# Mother_Board_Power.net
KiCad netlist of a schematic drawn in Altium Designer
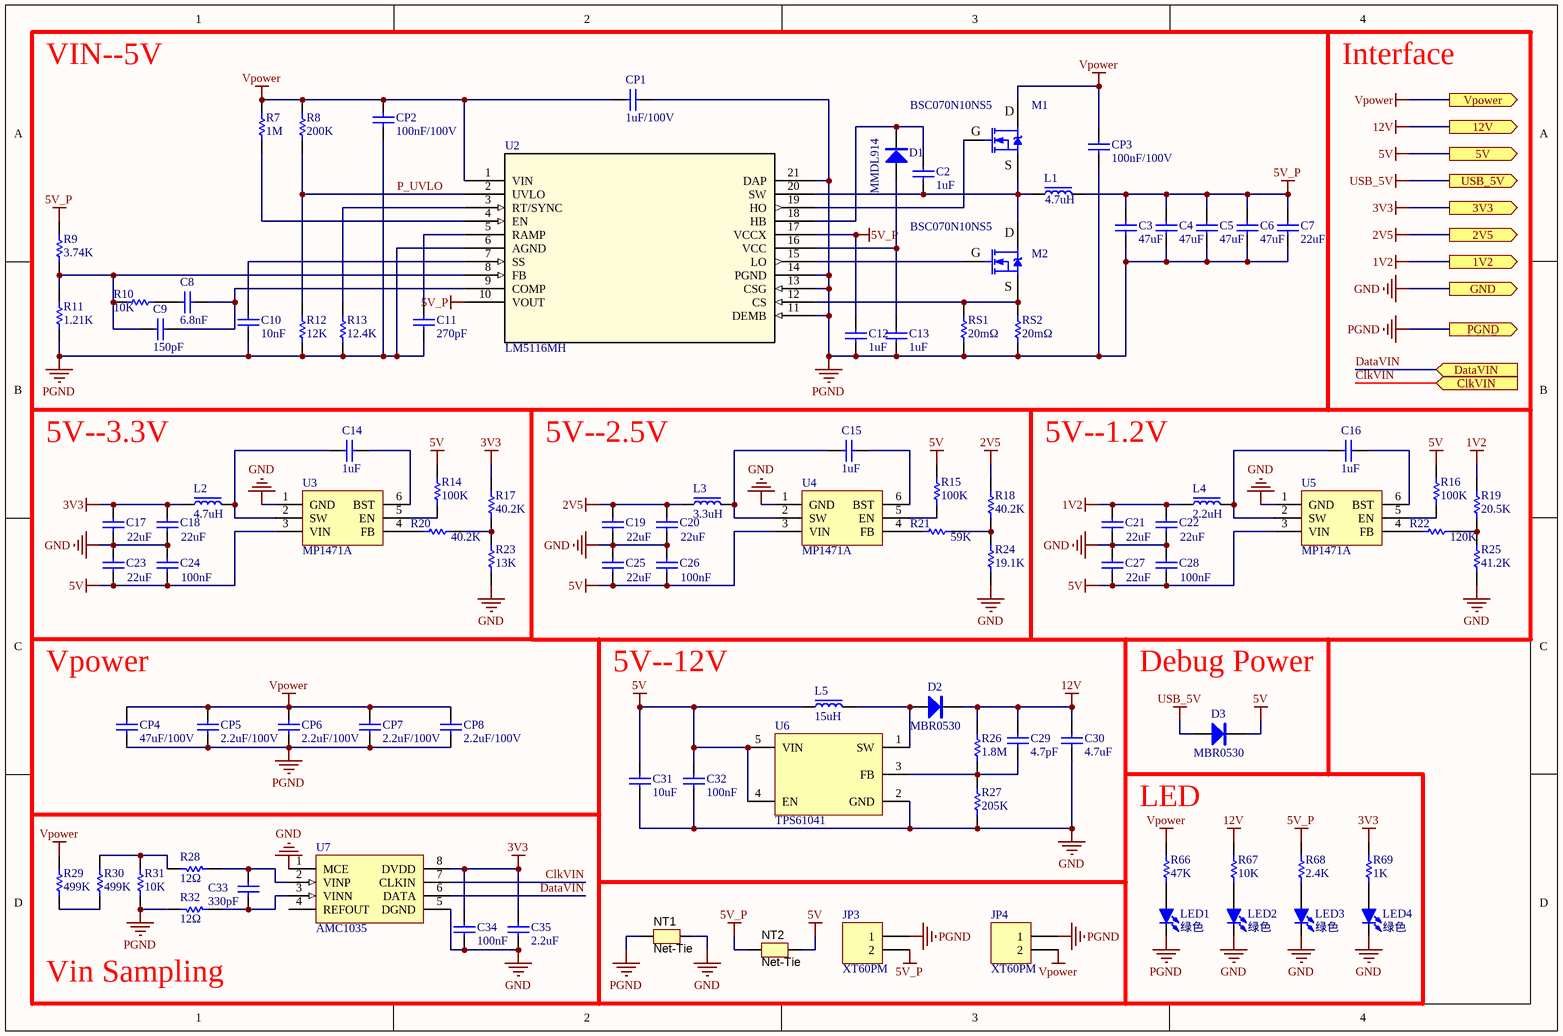
[diagram p0: Mother Board Power.SchDoc]

(export (version "E")
  (design (tool "Eeschema 10.0.6"))
  (components
    (comp (ref "C2") (value "1uF") (footprint "C0805") (libsource (lib "Cap") (part "Cap")))
    (comp (ref "C3") (value "47uF") (footprint "C0805") (libsource (lib "Cap") (part "Cap")))
    (comp (ref "C4") (value "47uF") (footprint "C0805") (libsource (lib "Cap") (part "Cap")))
    (comp (ref "C5") (value "47uF") (footprint "C0805") (libsource (lib "Cap") (part "Cap")))
    (comp (ref "C6") (value "47uF") (footprint "C0805") (libsource (lib "Cap") (part "Cap")))
    (comp (ref "C7") (value "22uF") (footprint "C0805") (libsource (lib "Cap") (part "Cap")))
    (comp (ref "C8") (value "6.8nF") (footprint "C0603") (libsource (lib "Cap") (part "Cap")))
    (comp (ref "C9") (value "150pF") (footprint "C0603") (libsource (lib "Cap") (part "Cap")))
    (comp (ref "C10") (value "10nF") (footprint "C0603") (libsource (lib "Cap") (part "Cap")))
    (comp (ref "C11") (value "270pF") (footprint "C0603") (libsource (lib "Cap") (part "Cap")))
    (comp (ref "C12") (value "1uF") (footprint "C0805") (libsource (lib "Cap") (part "Cap")))
    (comp (ref "C13") (value "1uF") (footprint "C0805") (libsource (lib "Cap") (part "Cap")))
    (comp (ref "C14") (value "1uF") (footprint "C0603") (libsource (lib "Cap") (part "Cap")))
    (comp (ref "C15") (value "1uF") (footprint "C0603") (libsource (lib "Cap") (part "Cap")))
    (comp (ref "C16") (value "1uF") (footprint "C0603") (libsource (lib "Cap") (part "Cap")))
    (comp (ref "C17") (value "22uF") (footprint "C0805") (libsource (lib "Cap") (part "Cap")))
    (comp (ref "C18") (value "22uF") (footprint "C0805") (libsource (lib "Cap") (part "Cap")))
    (comp (ref "C19") (value "22uF") (footprint "C0805") (libsource (lib "Cap") (part "Cap")))
    (comp (ref "C20") (value "22uF") (footprint "C0805") (libsource (lib "Cap") (part "Cap")))
    (comp (ref "C21") (value "22uF") (footprint "C0805") (libsource (lib "Cap") (part "Cap")))
    (comp (ref "C22") (value "22uF") (footprint "C0805") (libsource (lib "Cap") (part "Cap")))
    (comp (ref "C23") (value "22uF") (footprint "C0805") (libsource (lib "Cap") (part "Cap")))
    (comp (ref "C24") (value "100nF") (footprint "C0603") (libsource (lib "Cap") (part "Cap")))
    (comp (ref "C25") (value "22uF") (footprint "C0805") (libsource (lib "Cap") (part "Cap")))
    (comp (ref "C26") (value "100nF") (footprint "C0603") (libsource (lib "Cap") (part "Cap")))
    (comp (ref "C27") (value "22uF") (footprint "C0805") (libsource (lib "Cap") (part "Cap")))
    (comp (ref "C28") (value "100nF") (footprint "C0603") (libsource (lib "Cap") (part "Cap")))
    (comp (ref "C29") (value "4.7pF") (footprint "C0603") (libsource (lib "Cap") (part "Cap")))
    (comp (ref "C30") (value "4.7uF") (footprint "C0805") (libsource (lib "Cap") (part "Cap")))
    (comp (ref "C31") (value "10uF") (footprint "C0805") (libsource (lib "Cap") (part "Cap")))
    (comp (ref "C32") (value "100nF") (footprint "C0603") (libsource (lib "Cap") (part "Cap")))
    (comp (ref "C33") (value "330pF") (footprint "C0603") (libsource (lib "Cap") (part "Cap")))
    (comp (ref "C34") (value "100nF") (footprint "C0603") (libsource (lib "Cap") (part "Cap")))
    (comp (ref "C35") (value "2.2uF") (footprint "C0603") (libsource (lib "Cap") (part "Cap")))
    (comp (ref "CP1") (value "1uF/100V") (footprint "C1206") (libsource (lib "Cap") (part "Cap")))
    (comp (ref "CP2") (value "100nF/100V") (footprint "C1206") (libsource (lib "Cap") (part "Cap")))
    (comp (ref "CP3") (value "100nF/100V") (footprint "C1206") (libsource (lib "Cap") (part "Cap")))
    (comp (ref "CP4") (value "47uF/100V") (footprint "C1206") (libsource (lib "Cap") (part "Cap")))
    (comp (ref "CP5") (value "2.2uF/100V") (footprint "C1206") (libsource (lib "Cap") (part "Cap")))
    (comp (ref "CP6") (value "2.2uF/100V") (footprint "C1206") (libsource (lib "Cap") (part "Cap")))
    (comp (ref "CP7") (value "2.2uF/100V") (footprint "C1206") (libsource (lib "Cap") (part "Cap")))
    (comp (ref "CP8") (value "2.2uF/100V") (footprint "C1206") (libsource (lib "Cap") (part "Cap")))
    (comp (ref "D1")
      (value "MMDL914")
      (footprint "SOD-323")
      (description "100V 0.2A开关管")
      (libsource (lib "All lib") (part "MMDL914"))
    )
    (comp (ref "D2")
      (value "MBR0530")
      (footprint "SOD-123")
      (description "30V 0.5A")
      (libsource (lib "All lib") (part "MBR0530"))
    )
    (comp (ref "D3")
      (value "MBR0530")
      (footprint "SOD-123")
      (description "30V 0.5A")
      (libsource (lib "All lib") (part "MBR0530"))
    )
    (comp (ref "JP3") (value "XT60PM") (footprint "XT60PM") (libsource (lib "All lib") (part "XT60PM")))
    (comp (ref "JP4") (value "XT60PM") (footprint "XT60PM") (libsource (lib "All lib") (part "XT60PM")))
    (comp (ref "L1")
      (value "4.7uH")
      (footprint "L 1040")
      (description "功率屏蔽电感")
      (libsource (lib "All lib") (part "L-CDRH"))
    )
    (comp (ref "L2")
      (value "4.7uH")
      (footprint "L 0530")
      (description "功率屏蔽电感")
      (libsource (lib "All lib") (part "L-CDRH"))
    )
    (comp (ref "L3")
      (value "3.3uH")
      (footprint "L 0530")
      (description "功率屏蔽电感")
      (libsource (lib "All lib") (part "L-CDRH"))
    )
    (comp (ref "L4")
      (value "2.2uH")
      (footprint "L 0530")
      (description "功率屏蔽电感")
      (libsource (lib "All lib") (part "L-CDRH"))
    )
    (comp (ref "L5")
      (value "15uH")
      (footprint "L 0530")
      (description "功率屏蔽电感")
      (libsource (lib "All lib") (part "L-CDRH"))
    )
    (comp (ref "LED1")
      (value "绿色")
      (footprint "LED 0603G L")
      (description "贴片LED")
      (fields (field (name "版权归属") "源创客"))
      (libsource (lib "All lib") (part "LED-SMD"))
    )
    (comp (ref "LED2")
      (value "绿色")
      (footprint "LED 0603G L")
      (description "贴片LED")
      (fields (field (name "版权归属") "源创客"))
      (libsource (lib "All lib") (part "LED-SMD"))
    )
    (comp (ref "LED3")
      (value "绿色")
      (footprint "LED 0603G L")
      (description "贴片LED")
      (fields (field (name "版权归属") "源创客"))
      (libsource (lib "All lib") (part "LED-SMD"))
    )
    (comp (ref "LED4")
      (value "绿色")
      (footprint "LED 0603G L")
      (description "贴片LED")
      (fields (field (name "版权归属") "源创客"))
      (libsource (lib "All lib") (part "LED-SMD"))
    )
    (comp (ref "M1")
      (value "BSC070N10NS5")
      (footprint "TDSON-8")
      (description "N沟场效应管")
      (libsource (lib "All lib") (part "BSC070N10NS5"))
    )
    (comp (ref "M2")
      (value "BSC070N10NS5")
      (footprint "TDSON-8")
      (description "N沟场效应管")
      (libsource (lib "All lib") (part "BSC070N10NS5"))
    )
    (comp (ref "NT1")
      (value "Net-Tie")
      (footprint "Net-Tie_80mil")
      (description "Single point connection between nets.")
      (fields (field (name "SYMBOLCREATOR") "codlsc") (field (name "PUBLISHER") "Texas Instruments"))
      (libsource (lib "All lib") (part "Net-Tie"))
    )
    (comp (ref "NT2")
      (value "Net-Tie")
      (footprint "Net-Tie_80mil")
      (description "Single point connection between nets.")
      (fields (field (name "SYMBOLCREATOR") "codlsc") (field (name "PUBLISHER") "Texas Instruments"))
      (libsource (lib "All lib") (part "Net-Tie"))
    )
    (comp (ref "R7") (value "1M") (footprint "R0603") (libsource (lib "Res") (part "RES")))
    (comp (ref "R8") (value "200K") (footprint "R0603") (libsource (lib "Res") (part "RES")))
    (comp (ref "R9") (value "3.74K") (footprint "R0603") (libsource (lib "Res") (part "RES")))
    (comp (ref "R10") (value "10K") (footprint "R0603") (libsource (lib "Res") (part "RES")))
    (comp (ref "R11") (value "1.21K") (footprint "R0603") (libsource (lib "Res") (part "RES")))
    (comp (ref "R12") (value "12K") (footprint "R0603") (libsource (lib "Res") (part "RES")))
    (comp (ref "R13") (value "12.4K") (footprint "R0603") (libsource (lib "Res") (part "RES")))
    (comp (ref "R14") (value "100K") (footprint "R0603") (libsource (lib "Res") (part "RES")))
    (comp (ref "R15") (value "100K") (footprint "R0603") (libsource (lib "Res") (part "RES")))
    (comp (ref "R16") (value "100K") (footprint "R0603") (libsource (lib "Res") (part "RES")))
    (comp (ref "R17") (value "40.2K") (footprint "R0603") (libsource (lib "Res") (part "RES")))
    (comp (ref "R18") (value "40.2K") (footprint "R0603") (libsource (lib "Res") (part "RES")))
    (comp (ref "R19") (value "20.5K") (footprint "R0603") (libsource (lib "Res") (part "RES")))
    (comp (ref "R20") (value "40.2K") (footprint "R0603") (libsource (lib "Res") (part "RES")))
    (comp (ref "R21") (value "59K") (footprint "R0603") (libsource (lib "Res") (part "RES")))
    (comp (ref "R22") (value "120K") (footprint "R0603") (libsource (lib "Res") (part "RES")))
    (comp (ref "R23") (value "13K") (footprint "R0603") (libsource (lib "Res") (part "RES")))
    (comp (ref "R24") (value "19.1K") (footprint "R0603") (libsource (lib "Res") (part "RES")))
    (comp (ref "R25") (value "41.2K") (footprint "R0603") (libsource (lib "Res") (part "RES")))
    (comp (ref "R26") (value "1.8M") (footprint "R0603") (libsource (lib "Res") (part "RES")))
    (comp (ref "R27") (value "205K") (footprint "R0603") (libsource (lib "Res") (part "RES")))
    (comp (ref "R28") (value "12Ω") (footprint "R0603") (libsource (lib "Res") (part "RES")))
    (comp (ref "R29") (value "499K") (footprint "R0603") (libsource (lib "Res") (part "RES")))
    (comp (ref "R30") (value "499K") (footprint "R0603") (libsource (lib "Res") (part "RES")))
    (comp (ref "R31") (value "10K") (footprint "R0603") (libsource (lib "Res") (part "RES")))
    (comp (ref "R32") (value "12Ω") (footprint "R0603") (libsource (lib "Res") (part "RES")))
    (comp (ref "R66") (value "47K") (footprint "R0603") (libsource (lib "Res") (part "RES")))
    (comp (ref "R67") (value "10K") (footprint "R0603") (libsource (lib "Res") (part "RES")))
    (comp (ref "R68") (value "2.4K") (footprint "R0603") (libsource (lib "Res") (part "RES")))
    (comp (ref "R69") (value "1K") (footprint "R0603") (libsource (lib "Res") (part "RES")))
    (comp (ref "RS1") (value "20mΩ") (footprint "R1206") (libsource (lib "Res") (part "RES")))
    (comp (ref "RS2") (value "20mΩ") (footprint "R1206") (libsource (lib "Res") (part "RES")))
    (comp (ref "U2")
      (value "LM5116MH")
      (footprint "MXA20A_TEX-L")
      (description "No Description Available")
      (fields (field (name "COPYRIGHT") "Copyright (C) 2021 Ultra Librarian. All rights reserved."))
      (libsource (lib "All lib") (part "LM5116MH"))
    )
    (comp (ref "U3")
      (value "MP1471A")
      (footprint "SOT23-6L")
      (description "4.5-16V输入 DC-DC Buck 芯片")
      (libsource (lib "All lib") (part "MP1471A"))
    )
    (comp (ref "U4")
      (value "MP1471A")
      (footprint "SOT23-6L")
      (description "4.5-16V输入 DC-DC Buck 芯片")
      (libsource (lib "All lib") (part "MP1471A"))
    )
    (comp (ref "U5")
      (value "MP1471A")
      (footprint "SOT23-6L")
      (description "4.5-16V输入 DC-DC Buck 芯片")
      (libsource (lib "All lib") (part "MP1471A"))
    )
    (comp (ref "U6")
      (value "TPS61041")
      (footprint "SOT23-5L")
      (description "Boost DC-DC")
      (libsource (lib "All lib") (part "TPS6104x"))
    )
    (comp (ref "U7") (value "AMC1035") (footprint "SOP8_L") (libsource (lib "All lib") (part "AMC1035")))
  )
  (nets
    (net (code "1") (name "/ClkVIN") (class "Default")
      (node (ref "U7") (pin "7") (pinfunction "CLKIN_7") (pintype "passive"))
    )
    (net (code "2") (name "/DataVIN") (class "Default")
      (node (ref "U7") (pin "6") (pinfunction "DATA_6") (pintype "power_in"))
    )
    (net (code "3") (name "/P_UVLO") (class "Default")
      (node (ref "R12") (pin "1") (pinfunction "1_1") (pintype "passive"))
      (node (ref "R8") (pin "1") (pinfunction "1_1") (pintype "passive"))
      (node (ref "U2") (pin "2") (pinfunction "UVLO_2") (pintype "passive"))
    )
    (net (code "4") (name "1V2") (class "Default")
      (node (ref "C21") (pin "1") (pinfunction "1_1") (pintype "passive"))
      (node (ref "C22") (pin "1") (pinfunction "1_1") (pintype "passive"))
      (node (ref "L4") (pin "1") (pinfunction "1_1") (pintype "passive"))
      (node (ref "R19") (pin "2") (pinfunction "2_2") (pintype "passive"))
    )
    (net (code "5") (name "2V5") (class "Default")
      (node (ref "C19") (pin "1") (pinfunction "1_1") (pintype "passive"))
      (node (ref "C20") (pin "1") (pinfunction "1_1") (pintype "passive"))
      (node (ref "L3") (pin "1") (pinfunction "1_1") (pintype "passive"))
      (node (ref "R18") (pin "2") (pinfunction "2_2") (pintype "passive"))
    )
    (net (code "6") (name "3V3") (class "Default")
      (node (ref "C17") (pin "1") (pinfunction "1_1") (pintype "passive"))
      (node (ref "C18") (pin "1") (pinfunction "1_1") (pintype "passive"))
      (node (ref "C34") (pin "1") (pinfunction "1_1") (pintype "passive"))
      (node (ref "C35") (pin "1") (pinfunction "1_1") (pintype "passive"))
      (node (ref "L2") (pin "1") (pinfunction "1_1") (pintype "passive"))
      (node (ref "R17") (pin "2") (pinfunction "2_2") (pintype "passive"))
      (node (ref "R69") (pin "1") (pinfunction "1_1") (pintype "passive"))
      (node (ref "U7") (pin "8") (pinfunction "DVDD_8") (pintype "power_in"))
    )
    (net (code "7") (name "5V") (class "Default")
      (node (ref "C23") (pin "2") (pinfunction "2_2") (pintype "passive"))
      (node (ref "C24") (pin "2") (pinfunction "2_2") (pintype "passive"))
      (node (ref "C25") (pin "2") (pinfunction "2_2") (pintype "passive"))
      (node (ref "C26") (pin "2") (pinfunction "2_2") (pintype "passive"))
      (node (ref "C27") (pin "2") (pinfunction "2_2") (pintype "passive"))
      (node (ref "C28") (pin "2") (pinfunction "2_2") (pintype "passive"))
      (node (ref "C31") (pin "2") (pinfunction "2_2") (pintype "passive"))
      (node (ref "C32") (pin "2") (pinfunction "2_2") (pintype "passive"))
      (node (ref "D3") (pin "K") (pinfunction "K_K") (pintype "passive"))
      (node (ref "L5") (pin "1") (pinfunction "1_1") (pintype "passive"))
      (node (ref "NT2") (pin "2") (pinfunction "2_2") (pintype "passive"))
      (node (ref "R14") (pin "1") (pinfunction "1_1") (pintype "passive"))
      (node (ref "R15") (pin "1") (pinfunction "1_1") (pintype "passive"))
      (node (ref "R16") (pin "1") (pinfunction "1_1") (pintype "passive"))
      (node (ref "U3") (pin "3") (pinfunction "VIN_3") (pintype "power_in"))
      (node (ref "U4") (pin "3") (pinfunction "VIN_3") (pintype "power_in"))
      (node (ref "U5") (pin "3") (pinfunction "VIN_3") (pintype "power_in"))
      (node (ref "U6") (pin "4") (pinfunction "EN_4") (pintype "passive"))
      (node (ref "U6") (pin "5") (pinfunction "VIN_5") (pintype "passive"))
    )
    (net (code "8") (name "5V_P") (class "Default")
      (node (ref "C12") (pin "1") (pinfunction "1_1") (pintype "passive"))
      (node (ref "C3") (pin "1") (pinfunction "1_1") (pintype "passive"))
      (node (ref "C4") (pin "1") (pinfunction "1_1") (pintype "passive"))
      (node (ref "C5") (pin "1") (pinfunction "1_1") (pintype "passive"))
      (node (ref "C6") (pin "1") (pinfunction "1_1") (pintype "passive"))
      (node (ref "C7") (pin "1") (pinfunction "1_1") (pintype "passive"))
      (node (ref "JP3") (pin "2") (pinfunction "2_2") (pintype "passive"))
      (node (ref "L1") (pin "2") (pinfunction "2_2") (pintype "passive"))
      (node (ref "NT2") (pin "1") (pinfunction "1_1") (pintype "passive"))
      (node (ref "R68") (pin "1") (pinfunction "1_1") (pintype "passive"))
      (node (ref "R9") (pin "2") (pinfunction "2_2") (pintype "passive"))
      (node (ref "U2") (pin "10") (pinfunction "VOUT_10") (pintype "passive"))
      (node (ref "U2") (pin "17") (pinfunction "VCCX_17") (pintype "power_in"))
    )
    (net (code "9") (name "12V") (class "Default")
      (node (ref "C29") (pin "2") (pinfunction "2_2") (pintype "passive"))
      (node (ref "C30") (pin "2") (pinfunction "2_2") (pintype "passive"))
      (node (ref "D2") (pin "K") (pinfunction "K_K") (pintype "passive"))
      (node (ref "R26") (pin "1") (pinfunction "1_1") (pintype "passive"))
      (node (ref "R67") (pin "1") (pinfunction "1_1") (pintype "passive"))
    )
    (net (code "10") (name "GND") (class "Default")
      (node (ref "C17") (pin "2") (pinfunction "2_2") (pintype "passive"))
      (node (ref "C18") (pin "2") (pinfunction "2_2") (pintype "passive"))
      (node (ref "C19") (pin "2") (pinfunction "2_2") (pintype "passive"))
      (node (ref "C20") (pin "2") (pinfunction "2_2") (pintype "passive"))
      (node (ref "C21") (pin "2") (pinfunction "2_2") (pintype "passive"))
      (node (ref "C22") (pin "2") (pinfunction "2_2") (pintype "passive"))
      (node (ref "C23") (pin "1") (pinfunction "1_1") (pintype "passive"))
      (node (ref "C24") (pin "1") (pinfunction "1_1") (pintype "passive"))
      (node (ref "C25") (pin "1") (pinfunction "1_1") (pintype "passive"))
      (node (ref "C26") (pin "1") (pinfunction "1_1") (pintype "passive"))
      (node (ref "C27") (pin "1") (pinfunction "1_1") (pintype "passive"))
      (node (ref "C28") (pin "1") (pinfunction "1_1") (pintype "passive"))
      (node (ref "C30") (pin "1") (pinfunction "1_1") (pintype "passive"))
      (node (ref "C31") (pin "1") (pinfunction "1_1") (pintype "passive"))
      (node (ref "C32") (pin "1") (pinfunction "1_1") (pintype "passive"))
      (node (ref "C34") (pin "2") (pinfunction "2_2") (pintype "passive"))
      (node (ref "C35") (pin "2") (pinfunction "2_2") (pintype "passive"))
      (node (ref "LED2") (pin "K") (pinfunction "K_K") (pintype "passive"))
      (node (ref "LED3") (pin "K") (pinfunction "K_K") (pintype "passive"))
      (node (ref "LED4") (pin "K") (pinfunction "K_K") (pintype "passive"))
      (node (ref "NT1") (pin "2") (pinfunction "2_2") (pintype "passive"))
      (node (ref "R23") (pin "2") (pinfunction "2_2") (pintype "passive"))
      (node (ref "R24") (pin "2") (pinfunction "2_2") (pintype "passive"))
      (node (ref "R25") (pin "2") (pinfunction "2_2") (pintype "passive"))
      (node (ref "R27") (pin "2") (pinfunction "2_2") (pintype "passive"))
      (node (ref "U3") (pin "1") (pinfunction "GND_1") (pintype "power_in"))
      (node (ref "U4") (pin "1") (pinfunction "GND_1") (pintype "power_in"))
      (node (ref "U5") (pin "1") (pinfunction "GND_1") (pintype "power_in"))
      (node (ref "U6") (pin "2") (pinfunction "GND_2") (pintype "passive"))
      (node (ref "U7") (pin "1") (pinfunction "MCE_1") (pintype "power_in"))
      (node (ref "U7") (pin "5") (pinfunction "DGND_5") (pintype "power_in"))
    )
    (net (code "11") (name "Net-(C8-Pad1)") (class "Default")
      (node (ref "C8") (pin "1") (pinfunction "1_1") (pintype "passive"))
      (node (ref "R10") (pin "2") (pinfunction "2_2") (pintype "passive"))
    )
    (net (code "12") (name "Net-(LED1-PadA)") (class "Default")
      (node (ref "LED1") (pin "A") (pinfunction "A_A") (pintype "passive"))
      (node (ref "R66") (pin "2") (pinfunction "2_2") (pintype "passive"))
    )
    (net (code "13") (name "Net-(LED2-PadA)") (class "Default")
      (node (ref "LED2") (pin "A") (pinfunction "A_A") (pintype "passive"))
      (node (ref "R67") (pin "2") (pinfunction "2_2") (pintype "passive"))
    )
    (net (code "14") (name "Net-(LED3-PadA)") (class "Default")
      (node (ref "LED3") (pin "A") (pinfunction "A_A") (pintype "passive"))
      (node (ref "R68") (pin "2") (pinfunction "2_2") (pintype "passive"))
    )
    (net (code "15") (name "Net-(LED4-PadA)") (class "Default")
      (node (ref "LED4") (pin "A") (pinfunction "A_A") (pintype "passive"))
      (node (ref "R69") (pin "2") (pinfunction "2_2") (pintype "passive"))
    )
    (net (code "16") (name "Net-(R17-Pad1)") (class "Default")
      (node (ref "R17") (pin "1") (pinfunction "1_1") (pintype "passive"))
      (node (ref "R20") (pin "1") (pinfunction "1_1") (pintype "passive"))
      (node (ref "R23") (pin "1") (pinfunction "1_1") (pintype "passive"))
    )
    (net (code "17") (name "Net-(R18-Pad1)") (class "Default")
      (node (ref "R18") (pin "1") (pinfunction "1_1") (pintype "passive"))
      (node (ref "R21") (pin "1") (pinfunction "1_1") (pintype "passive"))
      (node (ref "R24") (pin "1") (pinfunction "1_1") (pintype "passive"))
    )
    (net (code "18") (name "Net-(R19-Pad1)") (class "Default")
      (node (ref "R19") (pin "1") (pinfunction "1_1") (pintype "passive"))
      (node (ref "R22") (pin "1") (pinfunction "1_1") (pintype "passive"))
      (node (ref "R25") (pin "1") (pinfunction "1_1") (pintype "passive"))
    )
    (net (code "19") (name "Net-(R28-Pad1)") (class "Default")
      (node (ref "R28") (pin "1") (pinfunction "1_1") (pintype "passive"))
      (node (ref "R30") (pin "1") (pinfunction "1_1") (pintype "passive"))
      (node (ref "R31") (pin "2") (pinfunction "2_2") (pintype "passive"))
    )
    (net (code "20") (name "Net-(R29-Pad1)") (class "Default")
      (node (ref "R29") (pin "1") (pinfunction "1_1") (pintype "passive"))
      (node (ref "R30") (pin "2") (pinfunction "2_2") (pintype "passive"))
    )
    (net (code "21") (name "Net-(U2-COMP)") (class "Default")
      (node (ref "C8") (pin "2") (pinfunction "2_2") (pintype "passive"))
      (node (ref "C9") (pin "2") (pinfunction "2_2") (pintype "passive"))
      (node (ref "U2") (pin "9") (pinfunction "COMP_9") (pintype "passive"))
    )
    (net (code "22") (name "Net-(U2-CS)") (class "Default")
      (node (ref "M2") (pin "S") (pinfunction "S_S") (pintype "passive"))
      (node (ref "RS1") (pin "2") (pinfunction "2_2") (pintype "passive"))
      (node (ref "RS2") (pin "2") (pinfunction "2_2") (pintype "passive"))
      (node (ref "U2") (pin "12") (pinfunction "CS_12") (pintype "input"))
    )
    (net (code "23") (name "Net-(U2-EN)") (class "Default")
      (node (ref "R7") (pin "2") (pinfunction "2_2") (pintype "passive"))
      (node (ref "U2") (pin "4") (pinfunction "EN_4") (pintype "input"))
    )
    (net (code "24") (name "Net-(U2-FB)") (class "Default")
      (node (ref "C9") (pin "1") (pinfunction "1_1") (pintype "passive"))
      (node (ref "R10") (pin "1") (pinfunction "1_1") (pintype "passive"))
      (node (ref "R11") (pin "1") (pinfunction "1_1") (pintype "passive"))
      (node (ref "R9") (pin "1") (pinfunction "1_1") (pintype "passive"))
      (node (ref "U2") (pin "8") (pinfunction "FB_8") (pintype "input"))
    )
    (net (code "25") (name "Net-(U2-HB)") (class "Default")
      (node (ref "C2") (pin "2") (pinfunction "2_2") (pintype "passive"))
      (node (ref "D1") (pin "K") (pinfunction "K_K") (pintype "passive"))
      (node (ref "U2") (pin "18") (pinfunction "HB_18") (pintype "passive"))
    )
    (net (code "26") (name "Net-(U2-HO)") (class "Default")
      (node (ref "M1") (pin "G") (pinfunction "G_G") (pintype "passive"))
      (node (ref "U2") (pin "19") (pinfunction "HO_19") (pintype "output"))
    )
    (net (code "27") (name "Net-(U2-LO)") (class "Default")
      (node (ref "M2") (pin "G") (pinfunction "G_G") (pintype "passive"))
      (node (ref "U2") (pin "15") (pinfunction "LO_15") (pintype "output"))
    )
    (net (code "28") (name "Net-(U2-RAMP)") (class "Default")
      (node (ref "C11") (pin "2") (pinfunction "2_2") (pintype "passive"))
      (node (ref "U2") (pin "5") (pinfunction "RAMP_5") (pintype "passive"))
    )
    (net (code "29") (name "Net-(U2-RT{slash}SYNC)") (class "Default")
      (node (ref "R13") (pin "1") (pinfunction "1_1") (pintype "passive"))
      (node (ref "U2") (pin "3") (pinfunction "RT/SYNC_3") (pintype "input"))
    )
    (net (code "30") (name "Net-(U2-SS)") (class "Default")
      (node (ref "C10") (pin "2") (pinfunction "2_2") (pintype "passive"))
      (node (ref "U2") (pin "7") (pinfunction "SS_7") (pintype "input"))
    )
    (net (code "31") (name "Net-(U2-SW)") (class "Default")
      (node (ref "C2") (pin "1") (pinfunction "1_1") (pintype "passive"))
      (node (ref "L1") (pin "1") (pinfunction "1_1") (pintype "passive"))
      (node (ref "M1") (pin "S") (pinfunction "S_S") (pintype "passive"))
      (node (ref "M2") (pin "D") (pinfunction "D_D") (pintype "passive"))
      (node (ref "U2") (pin "20") (pinfunction "SW_20") (pintype "power_in"))
    )
    (net (code "32") (name "Net-(U2-VCC)") (class "Default")
      (node (ref "C13") (pin "1") (pinfunction "1_1") (pintype "passive"))
      (node (ref "D1") (pin "A") (pinfunction "A_A") (pintype "passive"))
      (node (ref "U2") (pin "16") (pinfunction "VCC_16") (pintype "power_in"))
    )
    (net (code "33") (name "Net-(U3-BST)") (class "Default")
      (node (ref "C14") (pin "2") (pinfunction "2_2") (pintype "passive"))
      (node (ref "U3") (pin "6") (pinfunction "BST_6") (pintype "power_in"))
    )
    (net (code "34") (name "Net-(U3-EN)") (class "Default")
      (node (ref "R14") (pin "2") (pinfunction "2_2") (pintype "passive"))
      (node (ref "U3") (pin "5") (pinfunction "EN_5") (pintype "power_in"))
    )
    (net (code "35") (name "Net-(U3-FB)") (class "Default")
      (node (ref "R20") (pin "2") (pinfunction "2_2") (pintype "passive"))
      (node (ref "U3") (pin "4") (pinfunction "FB_4") (pintype "power_in"))
    )
    (net (code "36") (name "Net-(U3-SW)") (class "Default")
      (node (ref "C14") (pin "1") (pinfunction "1_1") (pintype "passive"))
      (node (ref "L2") (pin "2") (pinfunction "2_2") (pintype "passive"))
      (node (ref "U3") (pin "2") (pinfunction "SW_2") (pintype "power_in"))
    )
    (net (code "37") (name "Net-(U4-BST)") (class "Default")
      (node (ref "C15") (pin "2") (pinfunction "2_2") (pintype "passive"))
      (node (ref "U4") (pin "6") (pinfunction "BST_6") (pintype "power_in"))
    )
    (net (code "38") (name "Net-(U4-EN)") (class "Default")
      (node (ref "R15") (pin "2") (pinfunction "2_2") (pintype "passive"))
      (node (ref "U4") (pin "5") (pinfunction "EN_5") (pintype "power_in"))
    )
    (net (code "39") (name "Net-(U4-FB)") (class "Default")
      (node (ref "R21") (pin "2") (pinfunction "2_2") (pintype "passive"))
      (node (ref "U4") (pin "4") (pinfunction "FB_4") (pintype "power_in"))
    )
    (net (code "40") (name "Net-(U4-SW)") (class "Default")
      (node (ref "C15") (pin "1") (pinfunction "1_1") (pintype "passive"))
      (node (ref "L3") (pin "2") (pinfunction "2_2") (pintype "passive"))
      (node (ref "U4") (pin "2") (pinfunction "SW_2") (pintype "power_in"))
    )
    (net (code "41") (name "Net-(U5-BST)") (class "Default")
      (node (ref "C16") (pin "2") (pinfunction "2_2") (pintype "passive"))
      (node (ref "U5") (pin "6") (pinfunction "BST_6") (pintype "power_in"))
    )
    (net (code "42") (name "Net-(U5-EN)") (class "Default")
      (node (ref "R16") (pin "2") (pinfunction "2_2") (pintype "passive"))
      (node (ref "U5") (pin "5") (pinfunction "EN_5") (pintype "power_in"))
    )
    (net (code "43") (name "Net-(U5-FB)") (class "Default")
      (node (ref "R22") (pin "2") (pinfunction "2_2") (pintype "passive"))
      (node (ref "U5") (pin "4") (pinfunction "FB_4") (pintype "power_in"))
    )
    (net (code "44") (name "Net-(U5-SW)") (class "Default")
      (node (ref "C16") (pin "1") (pinfunction "1_1") (pintype "passive"))
      (node (ref "L4") (pin "2") (pinfunction "2_2") (pintype "passive"))
      (node (ref "U5") (pin "2") (pinfunction "SW_2") (pintype "power_in"))
    )
    (net (code "45") (name "Net-(U6-FB)") (class "Default")
      (node (ref "C29") (pin "1") (pinfunction "1_1") (pintype "passive"))
      (node (ref "R26") (pin "2") (pinfunction "2_2") (pintype "passive"))
      (node (ref "R27") (pin "1") (pinfunction "1_1") (pintype "passive"))
      (node (ref "U6") (pin "3") (pinfunction "FB_3") (pintype "passive"))
    )
    (net (code "46") (name "Net-(U6-SW)") (class "Default")
      (node (ref "D2") (pin "A") (pinfunction "A_A") (pintype "passive"))
      (node (ref "L5") (pin "2") (pinfunction "2_2") (pintype "passive"))
      (node (ref "U6") (pin "1") (pinfunction "SW_1") (pintype "passive"))
    )
    (net (code "47") (name "Net-(U7-VINN)") (class "Default")
      (node (ref "C33") (pin "1") (pinfunction "1_1") (pintype "passive"))
      (node (ref "R32") (pin "2") (pinfunction "2_2") (pintype "passive"))
      (node (ref "U7") (pin "3") (pinfunction "VINN_3") (pintype "input"))
    )
    (net (code "48") (name "Net-(U7-VINP)") (class "Default")
      (node (ref "C33") (pin "2") (pinfunction "2_2") (pintype "passive"))
      (node (ref "R28") (pin "2") (pinfunction "2_2") (pintype "passive"))
      (node (ref "U7") (pin "2") (pinfunction "VINP_2") (pintype "input"))
    )
    (net (code "49") (name "PGND") (class "Default")
      (node (ref "C10") (pin "1") (pinfunction "1_1") (pintype "passive"))
      (node (ref "C11") (pin "1") (pinfunction "1_1") (pintype "passive"))
      (node (ref "C12") (pin "2") (pinfunction "2_2") (pintype "passive"))
      (node (ref "C13") (pin "2") (pinfunction "2_2") (pintype "passive"))
      (node (ref "C3") (pin "2") (pinfunction "2_2") (pintype "passive"))
      (node (ref "C4") (pin "2") (pinfunction "2_2") (pintype "passive"))
      (node (ref "C5") (pin "2") (pinfunction "2_2") (pintype "passive"))
      (node (ref "C6") (pin "2") (pinfunction "2_2") (pintype "passive"))
      (node (ref "C7") (pin "2") (pinfunction "2_2") (pintype "passive"))
      (node (ref "CP1") (pin "2") (pinfunction "2_2") (pintype "passive"))
      (node (ref "CP2") (pin "1") (pinfunction "1_1") (pintype "passive"))
      (node (ref "CP3") (pin "1") (pinfunction "1_1") (pintype "passive"))
      (node (ref "CP4") (pin "2") (pinfunction "2_2") (pintype "passive"))
      (node (ref "CP5") (pin "2") (pinfunction "2_2") (pintype "passive"))
      (node (ref "CP6") (pin "2") (pinfunction "2_2") (pintype "passive"))
      (node (ref "CP7") (pin "2") (pinfunction "2_2") (pintype "passive"))
      (node (ref "CP8") (pin "2") (pinfunction "2_2") (pintype "passive"))
      (node (ref "JP3") (pin "1") (pinfunction "1_1") (pintype "passive"))
      (node (ref "JP4") (pin "1") (pinfunction "1_1") (pintype "passive"))
      (node (ref "LED1") (pin "K") (pinfunction "K_K") (pintype "passive"))
      (node (ref "NT1") (pin "1") (pinfunction "1_1") (pintype "passive"))
      (node (ref "R11") (pin "2") (pinfunction "2_2") (pintype "passive"))
      (node (ref "R12") (pin "2") (pinfunction "2_2") (pintype "passive"))
      (node (ref "R13") (pin "2") (pinfunction "2_2") (pintype "passive"))
      (node (ref "R31") (pin "1") (pinfunction "1_1") (pintype "passive"))
      (node (ref "R32") (pin "1") (pinfunction "1_1") (pintype "passive"))
      (node (ref "RS1") (pin "1") (pinfunction "1_1") (pintype "passive"))
      (node (ref "RS2") (pin "1") (pinfunction "1_1") (pintype "passive"))
      (node (ref "U2") (pin "11") (pinfunction "DEMB_11") (pintype "input"))
      (node (ref "U2") (pin "13") (pinfunction "CSG_13") (pintype "input"))
      (node (ref "U2") (pin "14") (pinfunction "PGND_14") (pintype "power_in"))
      (node (ref "U2") (pin "21") (pinfunction "DAP_21") (pintype "power_in"))
      (node (ref "U2") (pin "6") (pinfunction "AGND_6") (pintype "power_in"))
    )
    (net (code "50") (name "USB_5V") (class "Default")
      (node (ref "D3") (pin "A") (pinfunction "A_A") (pintype "passive"))
    )
    (net (code "51") (name "Vpower") (class "Default")
      (node (ref "CP1") (pin "1") (pinfunction "1_1") (pintype "passive"))
      (node (ref "CP2") (pin "2") (pinfunction "2_2") (pintype "passive"))
      (node (ref "CP3") (pin "2") (pinfunction "2_2") (pintype "passive"))
      (node (ref "CP4") (pin "1") (pinfunction "1_1") (pintype "passive"))
      (node (ref "CP5") (pin "1") (pinfunction "1_1") (pintype "passive"))
      (node (ref "CP6") (pin "1") (pinfunction "1_1") (pintype "passive"))
      (node (ref "CP7") (pin "1") (pinfunction "1_1") (pintype "passive"))
      (node (ref "CP8") (pin "1") (pinfunction "1_1") (pintype "passive"))
      (node (ref "JP4") (pin "2") (pinfunction "2_2") (pintype "passive"))
      (node (ref "M1") (pin "D") (pinfunction "D_D") (pintype "passive"))
      (node (ref "R29") (pin "2") (pinfunction "2_2") (pintype "passive"))
      (node (ref "R66") (pin "1") (pinfunction "1_1") (pintype "passive"))
      (node (ref "R7") (pin "1") (pinfunction "1_1") (pintype "passive"))
      (node (ref "R8") (pin "2") (pinfunction "2_2") (pintype "passive"))
      (node (ref "U2") (pin "1") (pinfunction "VIN_1") (pintype "power_in"))
    )
    (net (code "52") (name "unconnected-(U7-REFOUT-Pad4)") (class "Default")
      (node (ref "U7") (pin "4") (pinfunction "REFOUT_4") (pintype "power_in"))
    )
  )
)
